# S06_SOM2_C_D.net
KiCad netlist of a schematic drawn in Altium Designer
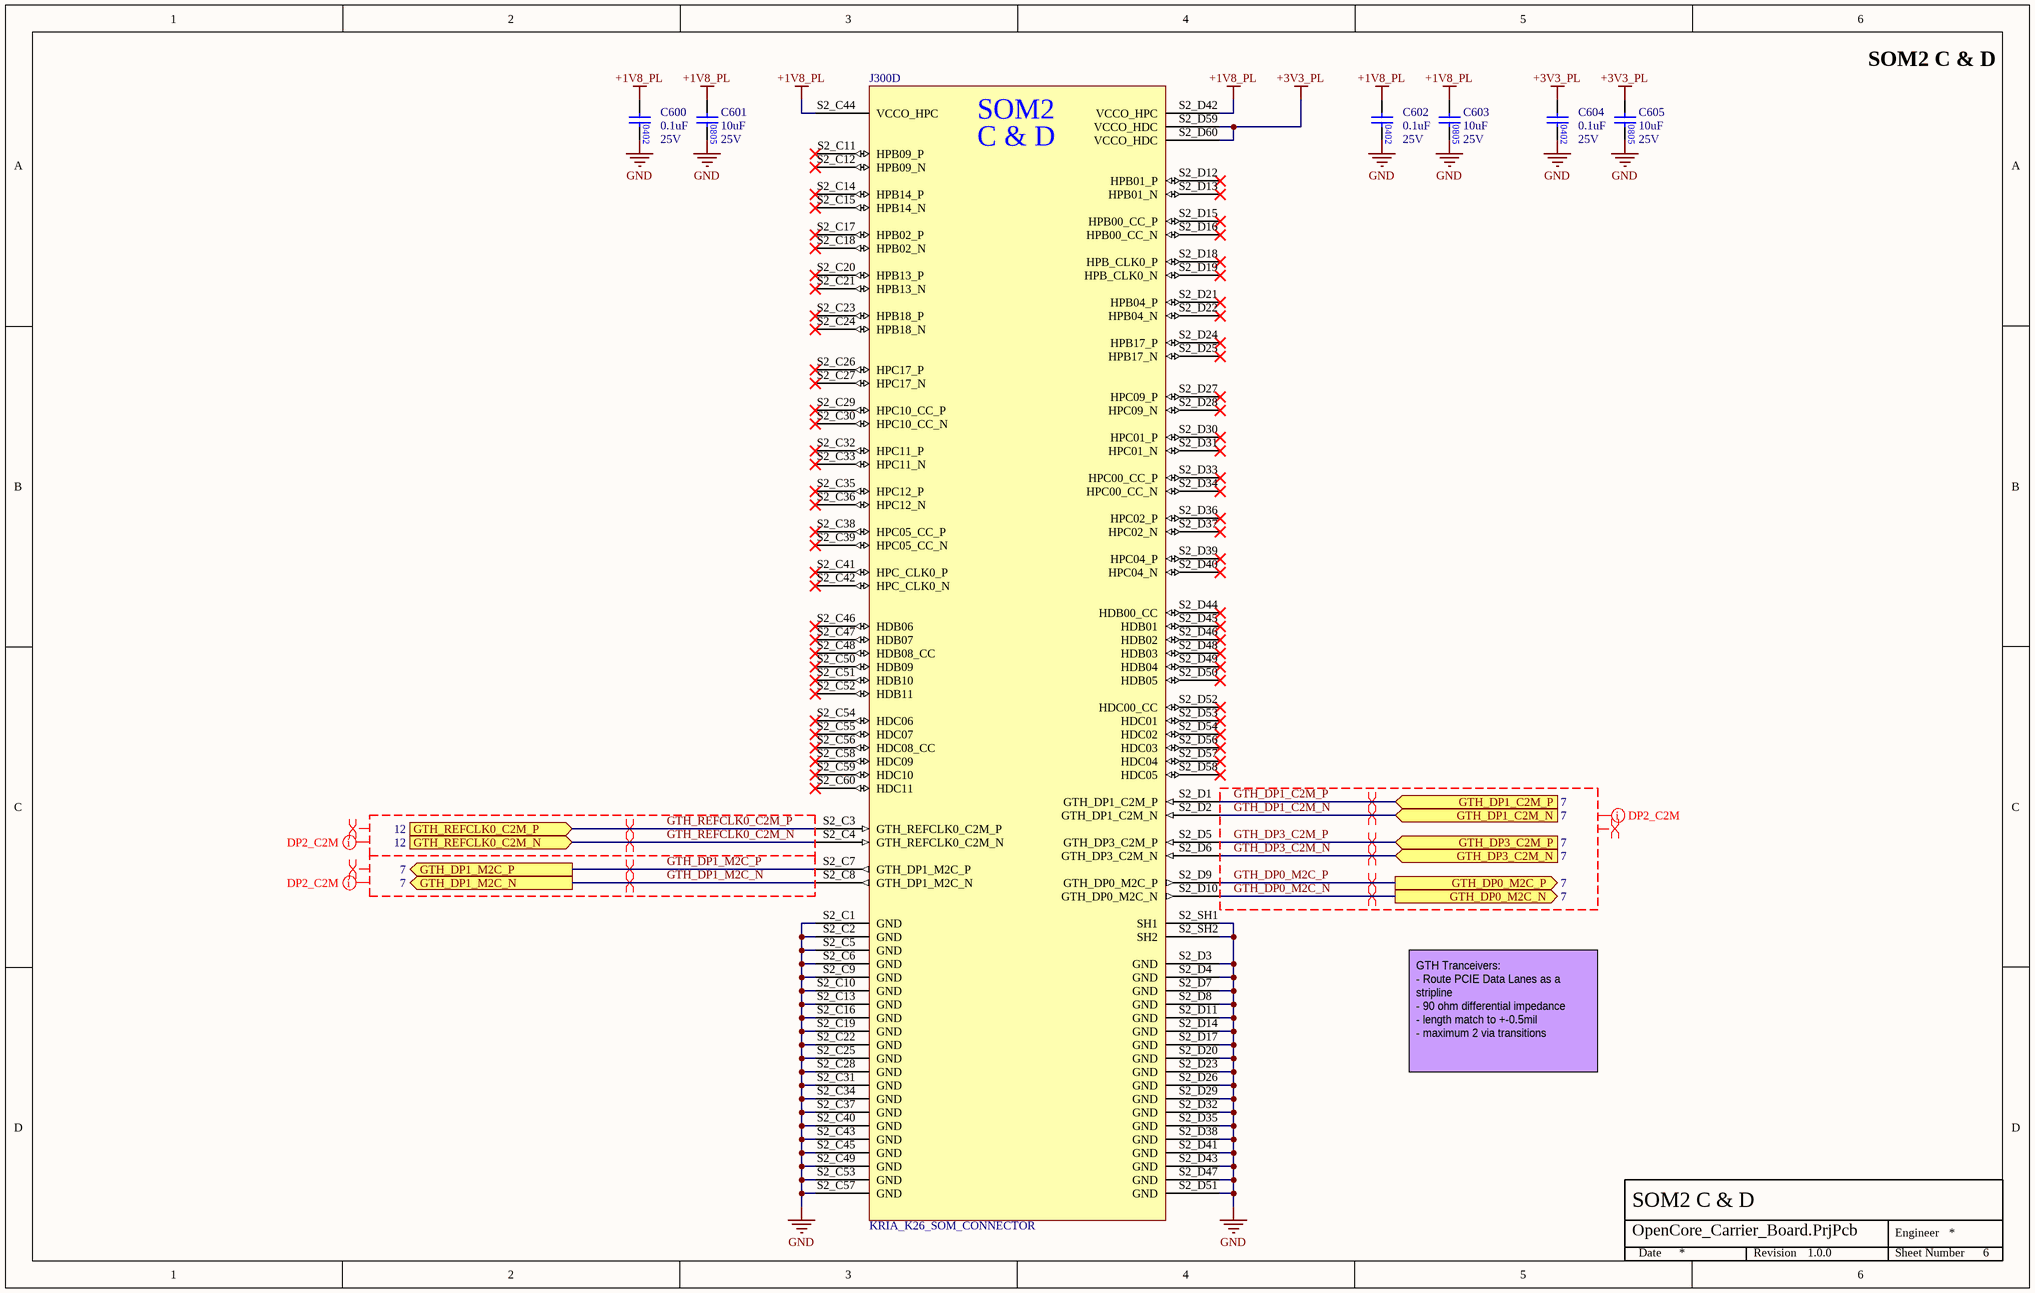
[diagram p0: S06_SOM2_C_D.SchDoc]

(export (version "E")
  (design (tool "Eeschema 10.0.6"))
  (components
    (comp (ref "C600")
      (value "0.1uF")
      (footprint "CAP0402")
      (description "CAP CER 0.1UF 25V X5R 0402")
      (fields
        (field (name "MANUFACTURER") "Samsung Electro-Mechanics")
        (field (name "TOLERANCE") "10%")
        (field (name "VOLTAGE RATING") "25V")
      )
      (libsource (lib "OpenCore_Sch_Lib") (part "CAP_CL05A104KA5NNNC"))
    )
    (comp (ref "C601")
      (value "10uF")
      (footprint "CAP0805")
      (description "CAP CER 10UF 25V X5R 0805")
      (fields
        (field (name "MANUFACTURER") "Samsung Electro-Mechanics")
        (field (name "TOLERANCE") "10%")
        (field (name "VOLTAGE RATING") "25V")
      )
      (libsource (lib "OpenCore_Sch_Lib") (part "CAP_CL21A106KAYNNNE"))
    )
    (comp (ref "C602")
      (value "0.1uF")
      (footprint "CAP0402")
      (description "CAP CER 0.1UF 25V X5R 0402")
      (fields
        (field (name "MANUFACTURER") "Samsung Electro-Mechanics")
        (field (name "TOLERANCE") "10%")
        (field (name "VOLTAGE RATING") "25V")
      )
      (libsource (lib "OpenCore_Sch_Lib") (part "CAP_CL05A104KA5NNNC"))
    )
    (comp (ref "C603")
      (value "10uF")
      (footprint "CAP0805")
      (description "CAP CER 10UF 25V X5R 0805")
      (fields
        (field (name "MANUFACTURER") "Samsung Electro-Mechanics")
        (field (name "TOLERANCE") "10%")
        (field (name "VOLTAGE RATING") "25V")
      )
      (libsource (lib "OpenCore_Sch_Lib") (part "CAP_CL21A106KAYNNNE"))
    )
    (comp (ref "C604")
      (value "0.1uF")
      (footprint "CAP0402")
      (description "CAP CER 0.1UF 25V X5R 0402")
      (fields
        (field (name "MANUFACTURER") "Samsung Electro-Mechanics")
        (field (name "TOLERANCE") "10%")
        (field (name "VOLTAGE RATING") "25V")
      )
      (libsource (lib "OpenCore_Sch_Lib") (part "CAP_CL05A104KA5NNNC"))
    )
    (comp (ref "C605")
      (value "10uF")
      (footprint "CAP0805")
      (description "CAP CER 10UF 25V X5R 0805")
      (fields
        (field (name "MANUFACTURER") "Samsung Electro-Mechanics")
        (field (name "TOLERANCE") "10%")
        (field (name "VOLTAGE RATING") "25V")
      )
      (libsource (lib "OpenCore_Sch_Lib") (part "CAP_CL21A106KAYNNNE"))
    )
    (comp (ref "J300")
      (value "KRIA_K26_SOM_CONNECTOR")
      (footprint "KRIA_K26_SOM")
      (description "2 x 240 pos Samtec REF-226081-01")
      (fields
        (field (name "MANUFACTURER") "Samtec")
        (field (name "MANUFACTURER PART NUMBER") "REF-226081-01")
      )
      (libsource (lib "OpenCore_Sch_Lib") (part "KRIA_K26_SOM"))
    )
  )
  (nets
    (net (code "1") (name "+1V8_PL") (class "Default")
      (node (ref "C600") (pin "1") (pinfunction "1_1") (pintype "passive"))
      (node (ref "C601") (pin "1") (pinfunction "1_1") (pintype "passive"))
      (node (ref "C602") (pin "1") (pinfunction "1_1") (pintype "passive"))
      (node (ref "C603") (pin "1") (pinfunction "1_1") (pintype "passive"))
      (node (ref "J300") (pin "S2_C44") (pinfunction "VCCO_HPC_S2_C44") (pintype "power_in"))
      (node (ref "J300") (pin "S2_D42") (pinfunction "VCCO_HPC_S2_D42") (pintype "power_in"))
    )
    (net (code "2") (name "+3V3_PL") (class "Default")
      (node (ref "C604") (pin "1") (pinfunction "1_1") (pintype "passive"))
      (node (ref "C605") (pin "1") (pinfunction "1_1") (pintype "passive"))
      (node (ref "J300") (pin "S2_D59") (pinfunction "VCCO_HDC_S2_D59") (pintype "power_in"))
      (node (ref "J300") (pin "S2_D60") (pinfunction "VCCO_HDC_S2_D60") (pintype "power_in"))
    )
    (net (code "3") (name "/GTH_DP0_M2C_N") (class "Default")
      (node (ref "J300") (pin "S2_D10") (pinfunction "GTH_DP0_M2C_N_S2_D10") (pintype "output"))
    )
    (net (code "4") (name "/GTH_DP0_M2C_P") (class "Default")
      (node (ref "J300") (pin "S2_D9") (pinfunction "GTH_DP0_M2C_P_S2_D9") (pintype "output"))
    )
    (net (code "5") (name "/GTH_DP1_C2M_N") (class "Default")
      (node (ref "J300") (pin "S2_D2") (pinfunction "GTH_DP1_C2M_N_S2_D2") (pintype "input"))
    )
    (net (code "6") (name "/GTH_DP1_C2M_P") (class "Default")
      (node (ref "J300") (pin "S2_D1") (pinfunction "GTH_DP1_C2M_P_S2_D1") (pintype "input"))
    )
    (net (code "7") (name "/GTH_DP1_M2C_N") (class "Default")
      (node (ref "J300") (pin "S2_C8") (pinfunction "GTH_DP1_M2C_N_S2_C8") (pintype "output"))
    )
    (net (code "8") (name "/GTH_DP1_M2C_P") (class "Default")
      (node (ref "J300") (pin "S2_C7") (pinfunction "GTH_DP1_M2C_P_S2_C7") (pintype "output"))
    )
    (net (code "9") (name "/GTH_DP3_C2M_N") (class "Default")
      (node (ref "J300") (pin "S2_D6") (pinfunction "GTH_DP3_C2M_N_S2_D6") (pintype "input"))
    )
    (net (code "10") (name "/GTH_DP3_C2M_P") (class "Default")
      (node (ref "J300") (pin "S2_D5") (pinfunction "GTH_DP3_C2M_P_S2_D5") (pintype "input"))
    )
    (net (code "11") (name "/GTH_REFCLK0_C2M_N") (class "Default")
      (node (ref "J300") (pin "S2_C4") (pinfunction "GTH_REFCLK0_C2M_N_S2_C4") (pintype "input"))
    )
    (net (code "12") (name "/GTH_REFCLK0_C2M_P") (class "Default")
      (node (ref "J300") (pin "S2_C3") (pinfunction "GTH_REFCLK0_C2M_P_S2_C3") (pintype "input"))
    )
    (net (code "13") (name "GND") (class "Default")
      (node (ref "C600") (pin "2") (pinfunction "2_2") (pintype "passive"))
      (node (ref "C601") (pin "2") (pinfunction "2_2") (pintype "passive"))
      (node (ref "C602") (pin "2") (pinfunction "2_2") (pintype "passive"))
      (node (ref "C603") (pin "2") (pinfunction "2_2") (pintype "passive"))
      (node (ref "C604") (pin "2") (pinfunction "2_2") (pintype "passive"))
      (node (ref "C605") (pin "2") (pinfunction "2_2") (pintype "passive"))
      (node (ref "J300") (pin "S2_C1") (pinfunction "GND_S2_C1") (pintype "power_in"))
      (node (ref "J300") (pin "S2_C10") (pinfunction "GND_S2_C10") (pintype "power_in"))
      (node (ref "J300") (pin "S2_C13") (pinfunction "GND_S2_C13") (pintype "power_in"))
      (node (ref "J300") (pin "S2_C16") (pinfunction "GND_S2_C16") (pintype "power_in"))
      (node (ref "J300") (pin "S2_C19") (pinfunction "GND_S2_C19") (pintype "power_in"))
      (node (ref "J300") (pin "S2_C2") (pinfunction "GND_S2_C2") (pintype "power_in"))
      (node (ref "J300") (pin "S2_C22") (pinfunction "GND_S2_C22") (pintype "power_in"))
      (node (ref "J300") (pin "S2_C25") (pinfunction "GND_S2_C25") (pintype "power_in"))
      (node (ref "J300") (pin "S2_C28") (pinfunction "GND_S2_C28") (pintype "power_in"))
      (node (ref "J300") (pin "S2_C31") (pinfunction "GND_S2_C31") (pintype "power_in"))
      (node (ref "J300") (pin "S2_C34") (pinfunction "GND_S2_C34") (pintype "power_in"))
      (node (ref "J300") (pin "S2_C37") (pinfunction "GND_S2_C37") (pintype "power_in"))
      (node (ref "J300") (pin "S2_C40") (pinfunction "GND_S2_C40") (pintype "power_in"))
      (node (ref "J300") (pin "S2_C43") (pinfunction "GND_S2_C43") (pintype "power_in"))
      (node (ref "J300") (pin "S2_C45") (pinfunction "GND_S2_C45") (pintype "power_in"))
      (node (ref "J300") (pin "S2_C49") (pinfunction "GND_S2_C49") (pintype "power_in"))
      (node (ref "J300") (pin "S2_C5") (pinfunction "GND_S2_C5") (pintype "power_in"))
      (node (ref "J300") (pin "S2_C53") (pinfunction "GND_S2_C53") (pintype "power_in"))
      (node (ref "J300") (pin "S2_C57") (pinfunction "GND_S2_C57") (pintype "power_in"))
      (node (ref "J300") (pin "S2_C6") (pinfunction "GND_S2_C6") (pintype "power_in"))
      (node (ref "J300") (pin "S2_C9") (pinfunction "GND_S2_C9") (pintype "power_in"))
      (node (ref "J300") (pin "S2_D11") (pinfunction "GND_S2_D11") (pintype "power_in"))
      (node (ref "J300") (pin "S2_D14") (pinfunction "GND_S2_D14") (pintype "power_in"))
      (node (ref "J300") (pin "S2_D17") (pinfunction "GND_S2_D17") (pintype "power_in"))
      (node (ref "J300") (pin "S2_D20") (pinfunction "GND_S2_D20") (pintype "power_in"))
      (node (ref "J300") (pin "S2_D23") (pinfunction "GND_S2_D23") (pintype "power_in"))
      (node (ref "J300") (pin "S2_D26") (pinfunction "GND_S2_D26") (pintype "power_in"))
      (node (ref "J300") (pin "S2_D29") (pinfunction "GND_S2_D29") (pintype "power_in"))
      (node (ref "J300") (pin "S2_D3") (pinfunction "GND_S2_D3") (pintype "power_in"))
      (node (ref "J300") (pin "S2_D32") (pinfunction "GND_S2_D32") (pintype "power_in"))
      (node (ref "J300") (pin "S2_D35") (pinfunction "GND_S2_D35") (pintype "power_in"))
      (node (ref "J300") (pin "S2_D38") (pinfunction "GND_S2_D38") (pintype "power_in"))
      (node (ref "J300") (pin "S2_D4") (pinfunction "GND_S2_D4") (pintype "power_in"))
      (node (ref "J300") (pin "S2_D41") (pinfunction "GND_S2_D41") (pintype "power_in"))
      (node (ref "J300") (pin "S2_D43") (pinfunction "GND_S2_D43") (pintype "power_in"))
      (node (ref "J300") (pin "S2_D47") (pinfunction "GND_S2_D47") (pintype "power_in"))
      (node (ref "J300") (pin "S2_D51") (pinfunction "GND_S2_D51") (pintype "power_in"))
      (node (ref "J300") (pin "S2_D7") (pinfunction "GND_S2_D7") (pintype "power_in"))
      (node (ref "J300") (pin "S2_D8") (pinfunction "GND_S2_D8") (pintype "power_in"))
      (node (ref "J300") (pin "S2_SH1") (pinfunction "SH1_S2_SH1") (pintype "passive"))
      (node (ref "J300") (pin "S2_SH2") (pinfunction "SH2_S2_SH2") (pintype "passive"))
    )
    (net (code "14") (name "unconnected-(J300D-HDB00_CC-PadS2_D44)") (class "Default")
      (node (ref "J300") (pin "S2_D44") (pinfunction "HDB00_CC_S2_D44") (pintype "bidirectional+no_connect"))
    )
    (net (code "15") (name "unconnected-(J300D-HDB01-PadS2_D45)") (class "Default")
      (node (ref "J300") (pin "S2_D45") (pinfunction "HDB01_S2_D45") (pintype "bidirectional+no_connect"))
    )
    (net (code "16") (name "unconnected-(J300D-HDB02-PadS2_D46)") (class "Default")
      (node (ref "J300") (pin "S2_D46") (pinfunction "HDB02_S2_D46") (pintype "bidirectional+no_connect"))
    )
    (net (code "17") (name "unconnected-(J300D-HDB03-PadS2_D48)") (class "Default")
      (node (ref "J300") (pin "S2_D48") (pinfunction "HDB03_S2_D48") (pintype "bidirectional+no_connect"))
    )
    (net (code "18") (name "unconnected-(J300D-HDB04-PadS2_D49)") (class "Default")
      (node (ref "J300") (pin "S2_D49") (pinfunction "HDB04_S2_D49") (pintype "bidirectional+no_connect"))
    )
    (net (code "19") (name "unconnected-(J300D-HDB05-PadS2_D50)") (class "Default")
      (node (ref "J300") (pin "S2_D50") (pinfunction "HDB05_S2_D50") (pintype "bidirectional+no_connect"))
    )
    (net (code "20") (name "unconnected-(J300D-HDB06-PadS2_C46)") (class "Default")
      (node (ref "J300") (pin "S2_C46") (pinfunction "HDB06_S2_C46") (pintype "bidirectional+no_connect"))
    )
    (net (code "21") (name "unconnected-(J300D-HDB07-PadS2_C47)") (class "Default")
      (node (ref "J300") (pin "S2_C47") (pinfunction "HDB07_S2_C47") (pintype "bidirectional+no_connect"))
    )
    (net (code "22") (name "unconnected-(J300D-HDB08_CC-PadS2_C48)") (class "Default")
      (node (ref "J300") (pin "S2_C48") (pinfunction "HDB08_CC_S2_C48") (pintype "bidirectional+no_connect"))
    )
    (net (code "23") (name "unconnected-(J300D-HDB09-PadS2_C50)") (class "Default")
      (node (ref "J300") (pin "S2_C50") (pinfunction "HDB09_S2_C50") (pintype "bidirectional+no_connect"))
    )
    (net (code "24") (name "unconnected-(J300D-HDB10-PadS2_C51)") (class "Default")
      (node (ref "J300") (pin "S2_C51") (pinfunction "HDB10_S2_C51") (pintype "bidirectional+no_connect"))
    )
    (net (code "25") (name "unconnected-(J300D-HDB11-PadS2_C52)") (class "Default")
      (node (ref "J300") (pin "S2_C52") (pinfunction "HDB11_S2_C52") (pintype "bidirectional+no_connect"))
    )
    (net (code "26") (name "unconnected-(J300D-HDC00_CC-PadS2_D52)") (class "Default")
      (node (ref "J300") (pin "S2_D52") (pinfunction "HDC00_CC_S2_D52") (pintype "bidirectional+no_connect"))
    )
    (net (code "27") (name "unconnected-(J300D-HDC01-PadS2_D53)") (class "Default")
      (node (ref "J300") (pin "S2_D53") (pinfunction "HDC01_S2_D53") (pintype "bidirectional+no_connect"))
    )
    (net (code "28") (name "unconnected-(J300D-HDC02-PadS2_D54)") (class "Default")
      (node (ref "J300") (pin "S2_D54") (pinfunction "HDC02_S2_D54") (pintype "bidirectional+no_connect"))
    )
    (net (code "29") (name "unconnected-(J300D-HDC03-PadS2_D56)") (class "Default")
      (node (ref "J300") (pin "S2_D56") (pinfunction "HDC03_S2_D56") (pintype "bidirectional+no_connect"))
    )
    (net (code "30") (name "unconnected-(J300D-HDC04-PadS2_D57)") (class "Default")
      (node (ref "J300") (pin "S2_D57") (pinfunction "HDC04_S2_D57") (pintype "bidirectional+no_connect"))
    )
    (net (code "31") (name "unconnected-(J300D-HDC05-PadS2_D58)") (class "Default")
      (node (ref "J300") (pin "S2_D58") (pinfunction "HDC05_S2_D58") (pintype "bidirectional+no_connect"))
    )
    (net (code "32") (name "unconnected-(J300D-HDC06-PadS2_C54)") (class "Default")
      (node (ref "J300") (pin "S2_C54") (pinfunction "HDC06_S2_C54") (pintype "bidirectional+no_connect"))
    )
    (net (code "33") (name "unconnected-(J300D-HDC07-PadS2_C55)") (class "Default")
      (node (ref "J300") (pin "S2_C55") (pinfunction "HDC07_S2_C55") (pintype "bidirectional+no_connect"))
    )
    (net (code "34") (name "unconnected-(J300D-HDC08_CC-PadS2_C56)") (class "Default")
      (node (ref "J300") (pin "S2_C56") (pinfunction "HDC08_CC_S2_C56") (pintype "bidirectional+no_connect"))
    )
    (net (code "35") (name "unconnected-(J300D-HDC09-PadS2_C58)") (class "Default")
      (node (ref "J300") (pin "S2_C58") (pinfunction "HDC09_S2_C58") (pintype "bidirectional+no_connect"))
    )
    (net (code "36") (name "unconnected-(J300D-HDC10-PadS2_C59)") (class "Default")
      (node (ref "J300") (pin "S2_C59") (pinfunction "HDC10_S2_C59") (pintype "bidirectional+no_connect"))
    )
    (net (code "37") (name "unconnected-(J300D-HDC11-PadS2_C60)") (class "Default")
      (node (ref "J300") (pin "S2_C60") (pinfunction "HDC11_S2_C60") (pintype "bidirectional+no_connect"))
    )
    (net (code "38") (name "unconnected-(J300D-HPB00_CC_N-PadS2_D16)") (class "Default")
      (node (ref "J300") (pin "S2_D16") (pinfunction "HPB00_CC_N_S2_D16") (pintype "bidirectional+no_connect"))
    )
    (net (code "39") (name "unconnected-(J300D-HPB00_CC_P-PadS2_D15)") (class "Default")
      (node (ref "J300") (pin "S2_D15") (pinfunction "HPB00_CC_P_S2_D15") (pintype "bidirectional+no_connect"))
    )
    (net (code "40") (name "unconnected-(J300D-HPB01_N-PadS2_D13)") (class "Default")
      (node (ref "J300") (pin "S2_D13") (pinfunction "HPB01_N_S2_D13") (pintype "bidirectional+no_connect"))
    )
    (net (code "41") (name "unconnected-(J300D-HPB01_P-PadS2_D12)") (class "Default")
      (node (ref "J300") (pin "S2_D12") (pinfunction "HPB01_P_S2_D12") (pintype "bidirectional+no_connect"))
    )
    (net (code "42") (name "unconnected-(J300D-HPB02_N-PadS2_C18)") (class "Default")
      (node (ref "J300") (pin "S2_C18") (pinfunction "HPB02_N_S2_C18") (pintype "bidirectional+no_connect"))
    )
    (net (code "43") (name "unconnected-(J300D-HPB02_P-PadS2_C17)") (class "Default")
      (node (ref "J300") (pin "S2_C17") (pinfunction "HPB02_P_S2_C17") (pintype "bidirectional+no_connect"))
    )
    (net (code "44") (name "unconnected-(J300D-HPB04_N-PadS2_D22)") (class "Default")
      (node (ref "J300") (pin "S2_D22") (pinfunction "HPB04_N_S2_D22") (pintype "bidirectional+no_connect"))
    )
    (net (code "45") (name "unconnected-(J300D-HPB04_P-PadS2_D21)") (class "Default")
      (node (ref "J300") (pin "S2_D21") (pinfunction "HPB04_P_S2_D21") (pintype "bidirectional+no_connect"))
    )
    (net (code "46") (name "unconnected-(J300D-HPB09_N-PadS2_C12)") (class "Default")
      (node (ref "J300") (pin "S2_C12") (pinfunction "HPB09_N_S2_C12") (pintype "bidirectional+no_connect"))
    )
    (net (code "47") (name "unconnected-(J300D-HPB09_P-PadS2_C11)") (class "Default")
      (node (ref "J300") (pin "S2_C11") (pinfunction "HPB09_P_S2_C11") (pintype "bidirectional+no_connect"))
    )
    (net (code "48") (name "unconnected-(J300D-HPB13_N-PadS2_C21)") (class "Default")
      (node (ref "J300") (pin "S2_C21") (pinfunction "HPB13_N_S2_C21") (pintype "bidirectional+no_connect"))
    )
    (net (code "49") (name "unconnected-(J300D-HPB13_P-PadS2_C20)") (class "Default")
      (node (ref "J300") (pin "S2_C20") (pinfunction "HPB13_P_S2_C20") (pintype "bidirectional+no_connect"))
    )
    (net (code "50") (name "unconnected-(J300D-HPB14_N-PadS2_C15)") (class "Default")
      (node (ref "J300") (pin "S2_C15") (pinfunction "HPB14_N_S2_C15") (pintype "bidirectional+no_connect"))
    )
    (net (code "51") (name "unconnected-(J300D-HPB14_P-PadS2_C14)") (class "Default")
      (node (ref "J300") (pin "S2_C14") (pinfunction "HPB14_P_S2_C14") (pintype "bidirectional+no_connect"))
    )
    (net (code "52") (name "unconnected-(J300D-HPB17_N-PadS2_D25)") (class "Default")
      (node (ref "J300") (pin "S2_D25") (pinfunction "HPB17_N_S2_D25") (pintype "bidirectional+no_connect"))
    )
    (net (code "53") (name "unconnected-(J300D-HPB17_P-PadS2_D24)") (class "Default")
      (node (ref "J300") (pin "S2_D24") (pinfunction "HPB17_P_S2_D24") (pintype "bidirectional+no_connect"))
    )
    (net (code "54") (name "unconnected-(J300D-HPB18_N-PadS2_C24)") (class "Default")
      (node (ref "J300") (pin "S2_C24") (pinfunction "HPB18_N_S2_C24") (pintype "bidirectional+no_connect"))
    )
    (net (code "55") (name "unconnected-(J300D-HPB18_P-PadS2_C23)") (class "Default")
      (node (ref "J300") (pin "S2_C23") (pinfunction "HPB18_P_S2_C23") (pintype "bidirectional+no_connect"))
    )
    (net (code "56") (name "unconnected-(J300D-HPB_CLK0_N-PadS2_D19)") (class "Default")
      (node (ref "J300") (pin "S2_D19") (pinfunction "HPB_CLK0_N_S2_D19") (pintype "bidirectional+no_connect"))
    )
    (net (code "57") (name "unconnected-(J300D-HPB_CLK0_P-PadS2_D18)") (class "Default")
      (node (ref "J300") (pin "S2_D18") (pinfunction "HPB_CLK0_P_S2_D18") (pintype "bidirectional+no_connect"))
    )
    (net (code "58") (name "unconnected-(J300D-HPC00_CC_N-PadS2_D34)") (class "Default")
      (node (ref "J300") (pin "S2_D34") (pinfunction "HPC00_CC_N_S2_D34") (pintype "bidirectional+no_connect"))
    )
    (net (code "59") (name "unconnected-(J300D-HPC00_CC_P-PadS2_D33)") (class "Default")
      (node (ref "J300") (pin "S2_D33") (pinfunction "HPC00_CC_P_S2_D33") (pintype "bidirectional+no_connect"))
    )
    (net (code "60") (name "unconnected-(J300D-HPC01_N-PadS2_D31)") (class "Default")
      (node (ref "J300") (pin "S2_D31") (pinfunction "HPC01_N_S2_D31") (pintype "bidirectional+no_connect"))
    )
    (net (code "61") (name "unconnected-(J300D-HPC01_P-PadS2_D30)") (class "Default")
      (node (ref "J300") (pin "S2_D30") (pinfunction "HPC01_P_S2_D30") (pintype "bidirectional+no_connect"))
    )
    (net (code "62") (name "unconnected-(J300D-HPC02_N-PadS2_D37)") (class "Default")
      (node (ref "J300") (pin "S2_D37") (pinfunction "HPC02_N_S2_D37") (pintype "bidirectional+no_connect"))
    )
    (net (code "63") (name "unconnected-(J300D-HPC02_P-PadS2_D36)") (class "Default")
      (node (ref "J300") (pin "S2_D36") (pinfunction "HPC02_P_S2_D36") (pintype "bidirectional+no_connect"))
    )
    (net (code "64") (name "unconnected-(J300D-HPC04_N-PadS2_D40)") (class "Default")
      (node (ref "J300") (pin "S2_D40") (pinfunction "HPC04_N_S2_D40") (pintype "bidirectional+no_connect"))
    )
    (net (code "65") (name "unconnected-(J300D-HPC04_P-PadS2_D39)") (class "Default")
      (node (ref "J300") (pin "S2_D39") (pinfunction "HPC04_P_S2_D39") (pintype "bidirectional+no_connect"))
    )
    (net (code "66") (name "unconnected-(J300D-HPC05_CC_N-PadS2_C39)") (class "Default")
      (node (ref "J300") (pin "S2_C39") (pinfunction "HPC05_CC_N_S2_C39") (pintype "bidirectional+no_connect"))
    )
    (net (code "67") (name "unconnected-(J300D-HPC05_CC_P-PadS2_C38)") (class "Default")
      (node (ref "J300") (pin "S2_C38") (pinfunction "HPC05_CC_P_S2_C38") (pintype "bidirectional+no_connect"))
    )
    (net (code "68") (name "unconnected-(J300D-HPC09_N-PadS2_D28)") (class "Default")
      (node (ref "J300") (pin "S2_D28") (pinfunction "HPC09_N_S2_D28") (pintype "bidirectional+no_connect"))
    )
    (net (code "69") (name "unconnected-(J300D-HPC09_P-PadS2_D27)") (class "Default")
      (node (ref "J300") (pin "S2_D27") (pinfunction "HPC09_P_S2_D27") (pintype "bidirectional+no_connect"))
    )
    (net (code "70") (name "unconnected-(J300D-HPC10_CC_N-PadS2_C30)") (class "Default")
      (node (ref "J300") (pin "S2_C30") (pinfunction "HPC10_CC_N_S2_C30") (pintype "bidirectional+no_connect"))
    )
    (net (code "71") (name "unconnected-(J300D-HPC10_CC_P-PadS2_C29)") (class "Default")
      (node (ref "J300") (pin "S2_C29") (pinfunction "HPC10_CC_P_S2_C29") (pintype "bidirectional+no_connect"))
    )
    (net (code "72") (name "unconnected-(J300D-HPC11_N-PadS2_C33)") (class "Default")
      (node (ref "J300") (pin "S2_C33") (pinfunction "HPC11_N_S2_C33") (pintype "bidirectional+no_connect"))
    )
    (net (code "73") (name "unconnected-(J300D-HPC11_P-PadS2_C32)") (class "Default")
      (node (ref "J300") (pin "S2_C32") (pinfunction "HPC11_P_S2_C32") (pintype "bidirectional+no_connect"))
    )
    (net (code "74") (name "unconnected-(J300D-HPC12_N-PadS2_C36)") (class "Default")
      (node (ref "J300") (pin "S2_C36") (pinfunction "HPC12_N_S2_C36") (pintype "bidirectional+no_connect"))
    )
    (net (code "75") (name "unconnected-(J300D-HPC12_P-PadS2_C35)") (class "Default")
      (node (ref "J300") (pin "S2_C35") (pinfunction "HPC12_P_S2_C35") (pintype "bidirectional+no_connect"))
    )
    (net (code "76") (name "unconnected-(J300D-HPC17_N-PadS2_C27)") (class "Default")
      (node (ref "J300") (pin "S2_C27") (pinfunction "HPC17_N_S2_C27") (pintype "bidirectional+no_connect"))
    )
    (net (code "77") (name "unconnected-(J300D-HPC17_P-PadS2_C26)") (class "Default")
      (node (ref "J300") (pin "S2_C26") (pinfunction "HPC17_P_S2_C26") (pintype "bidirectional+no_connect"))
    )
    (net (code "78") (name "unconnected-(J300D-HPC_CLK0_N-PadS2_C42)") (class "Default")
      (node (ref "J300") (pin "S2_C42") (pinfunction "HPC_CLK0_N_S2_C42") (pintype "bidirectional+no_connect"))
    )
    (net (code "79") (name "unconnected-(J300D-HPC_CLK0_P-PadS2_C41)") (class "Default")
      (node (ref "J300") (pin "S2_C41") (pinfunction "HPC_CLK0_P_S2_C41") (pintype "bidirectional+no_connect"))
    )
  )
)
